# MCU.net
KiCad netlist of a schematic drawn in Altium Designer
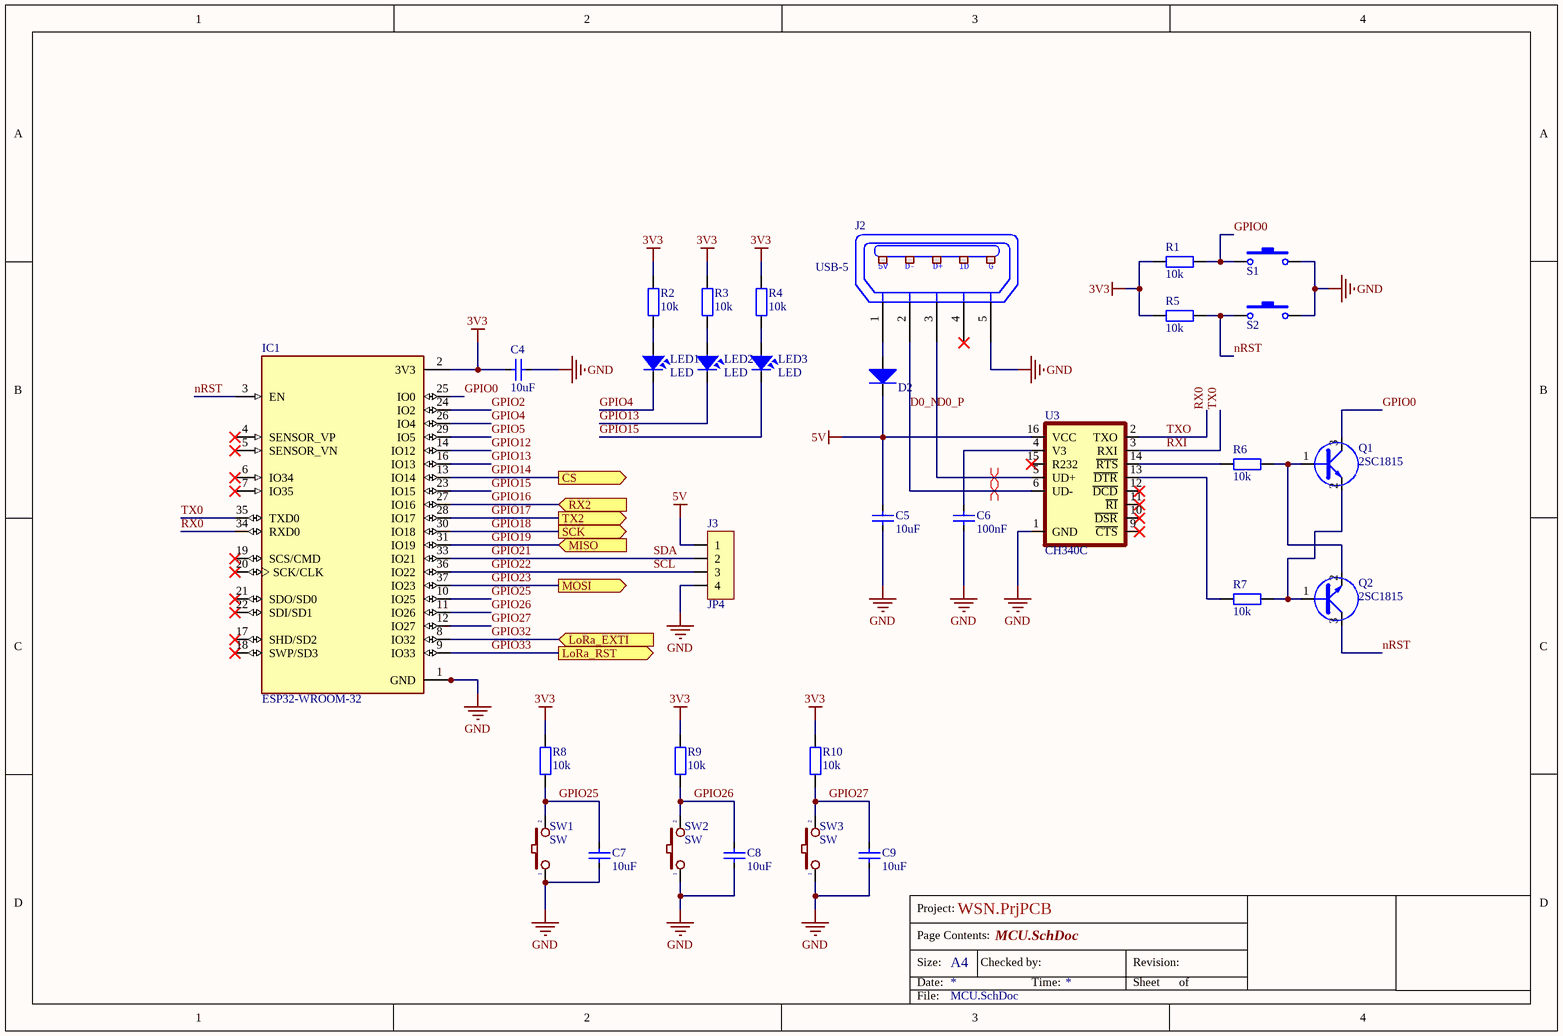
[diagram p0: MCU.SchDoc]

(export (version "E")
  (design (tool "Eeschema 10.0.6"))
  (components
    (comp (ref "C4")
      (value "10uF")
      (footprint "CAP_0805")
      (description "Capacitor")
      (fields (field (name "PUBLISHER") "Altium Limited"))
      (libsource (lib "My Library") (part "CapSMD"))
    )
    (comp (ref "C5")
      (value "10uF")
      (footprint "CAP_0805")
      (description "Capacitor")
      (fields (field (name "PUBLISHER") "Altium Limited"))
      (libsource (lib "My Library") (part "CapSMD"))
    )
    (comp (ref "C6")
      (value "100nF")
      (footprint "CAP_0805")
      (description "Capacitor")
      (fields (field (name "PUBLISHER") "Altium Limited"))
      (libsource (lib "My Library") (part "CapSMD"))
    )
    (comp (ref "C7")
      (value "10uF")
      (footprint "CAP_0805")
      (description "Capacitor")
      (fields (field (name "PUBLISHER") "Altium Limited"))
      (libsource (lib "My Library") (part "CapSMD"))
    )
    (comp (ref "C8")
      (value "10uF")
      (footprint "CAP_0805")
      (description "Capacitor")
      (fields (field (name "PUBLISHER") "Altium Limited"))
      (libsource (lib "My Library") (part "CapSMD"))
    )
    (comp (ref "C9")
      (value "10uF")
      (footprint "CAP_0805")
      (description "Capacitor")
      (fields (field (name "PUBLISHER") "Altium Limited"))
      (libsource (lib "My Library") (part "CapSMD"))
    )
    (comp (ref "D2")
      (value "Diode SMD")
      (footprint "DIO-214AC(SMA)")
      (description "Default Diode")
      (fields (field (name "PUBLISHER") "Altium Limited"))
      (libsource (lib "My Library") (part "Diode SMD"))
    )
    (comp (ref "IC1")
      (value "ESP32-WROOM-32")
      (footprint "MODULE_ESP32-WROOM-32")
      (description "Bluetooth, WiFi Transceiver Module 2.4GHz ~ 2.5GHz Surface Mount")
      (fields (field (name "MF") "Espressif Systems") (field (name "DIGI-KEY_PART_NUMBER") "1904-1010-1-ND"))
      (libsource (lib "My Library") (part "ESP32-WROOM-32"))
    )
    (comp (ref "J2")
      (value "USB-5")
      (footprint "USB-M1")
      (fields
        (field (name "MANUFACTURER") "FCI")
        (field (name "MANUFACTURER PART NUMBER") "10118193-0001LF")
        (field (name ".CREATOR") "MM")
        (field (name ".CHECKED PCB") "RF")
        (field (name ".CHECKED SCH") "MM")
      )
      (libsource (lib "My Library") (part "USB-5"))
    )
    (comp (ref "J3")
      (value "JP4")
      (footprint "JP4-C1T")
      (description "WR-PHD 2.54 mm Angled Socket Header")
      (fields
        (field (name "MANUFACTURER") "Würth Elektronik eiSos GmbH")
        (field (name "PARTNO") "613004143121")
        (field (name "CREATED BY") "Karrer Zheng")
      )
      (libsource (lib "My Library") (part "JP4"))
    )
    (comp (ref "LED1")
      (value "LED")
      (footprint "LED-0805-Orange")
      (description "LED Single colour Green and Red")
      (libsource (lib "My Library") (part "LED"))
    )
    (comp (ref "LED2")
      (value "LED")
      (footprint "LED-0805-Orange")
      (description "LED Single colour Green and Red")
      (libsource (lib "My Library") (part "LED"))
    )
    (comp (ref "LED3")
      (value "LED")
      (footprint "LED-0805-Orange")
      (description "LED Single colour Green and Red")
      (libsource (lib "My Library") (part "LED"))
    )
    (comp (ref "Q1")
      (value "2SC1815")
      (footprint "SOT23D")
      (description "NPN 600mW, ECB")
      (libsource (lib "My Library") (part "C1815"))
    )
    (comp (ref "Q2")
      (value "2SC1815")
      (footprint "SOT23D")
      (description "NPN 600mW, ECB")
      (libsource (lib "") (part "C1815_1"))
    )
    (comp (ref "R1")
      (value "10k")
      (footprint "RES-SMD-0805")
      (description "Resistor SMD")
      (fields
        (field (name "MANUFACTURER") "Generic Components")
        (field (name "PUBLISHER") "Altium Hobart Technology Centre")
      )
      (libsource (lib "My Library") (part "Resistor - SMD"))
    )
    (comp (ref "R2")
      (value "10k")
      (footprint "RES-SMD-0805")
      (description "Resistor SMD")
      (fields
        (field (name "MANUFACTURER") "Generic Components")
        (field (name "PUBLISHER") "Altium Hobart Technology Centre")
      )
      (libsource (lib "My Library") (part "Resistor - SMD"))
    )
    (comp (ref "R3")
      (value "10k")
      (footprint "RES-SMD-0805")
      (description "Resistor SMD")
      (fields
        (field (name "MANUFACTURER") "Generic Components")
        (field (name "PUBLISHER") "Altium Hobart Technology Centre")
      )
      (libsource (lib "My Library") (part "Resistor - SMD"))
    )
    (comp (ref "R4")
      (value "10k")
      (footprint "RES-SMD-0805")
      (description "Resistor SMD")
      (fields
        (field (name "MANUFACTURER") "Generic Components")
        (field (name "PUBLISHER") "Altium Hobart Technology Centre")
      )
      (libsource (lib "My Library") (part "Resistor - SMD"))
    )
    (comp (ref "R5")
      (value "10k")
      (footprint "RES-SMD-0805")
      (description "Resistor SMD")
      (fields
        (field (name "MANUFACTURER") "Generic Components")
        (field (name "PUBLISHER") "Altium Hobart Technology Centre")
      )
      (libsource (lib "My Library") (part "Resistor - SMD"))
    )
    (comp (ref "R6")
      (value "10k")
      (footprint "RES-SMD-0805")
      (description "Resistor SMD")
      (fields
        (field (name "MANUFACTURER") "Generic Components")
        (field (name "PUBLISHER") "Altium Hobart Technology Centre")
      )
      (libsource (lib "My Library") (part "Resistor - SMD"))
    )
    (comp (ref "R7")
      (value "10k")
      (footprint "RES-SMD-0805")
      (description "Resistor SMD")
      (fields
        (field (name "MANUFACTURER") "Generic Components")
        (field (name "PUBLISHER") "Altium Hobart Technology Centre")
      )
      (libsource (lib "My Library") (part "Resistor - SMD"))
    )
    (comp (ref "R8")
      (value "10k")
      (footprint "RES-SMD-0805")
      (description "Resistor SMD")
      (fields
        (field (name "MANUFACTURER") "Generic Components")
        (field (name "PUBLISHER") "Altium Hobart Technology Centre")
      )
      (libsource (lib "My Library") (part "Resistor - SMD"))
    )
    (comp (ref "R9")
      (value "10k")
      (footprint "RES-SMD-0805")
      (description "Resistor SMD")
      (fields
        (field (name "MANUFACTURER") "Generic Components")
        (field (name "PUBLISHER") "Altium Hobart Technology Centre")
      )
      (libsource (lib "My Library") (part "Resistor - SMD"))
    )
    (comp (ref "R10")
      (value "10k")
      (footprint "RES-SMD-0805")
      (description "Resistor SMD")
      (fields
        (field (name "MANUFACTURER") "Generic Components")
        (field (name "PUBLISHER") "Altium Hobart Technology Centre")
      )
      (libsource (lib "My Library") (part "Resistor - SMD"))
    )
    (comp (ref "S1")
      (value "SW-SMD")
      (footprint "SW 3x2x4")
      (description "Switch")
      (fields (field (name "PUBLISHER") "Altium Limited"))
      (libsource (lib "My Library") (part "SW-SMD"))
    )
    (comp (ref "S2")
      (value "SW-SMD")
      (footprint "SW 3x2x4")
      (description "Switch")
      (fields (field (name "PUBLISHER") "Altium Limited"))
      (libsource (lib "My Library") (part "SW-SMD"))
    )
    (comp (ref "SW1")
      (value "SW")
      (footprint "SW2")
      (description "Switch button 2 pin")
      (libsource (lib "My Library") (part "SW2"))
    )
    (comp (ref "SW2")
      (value "SW")
      (footprint "SW2")
      (description "Switch button 2 pin")
      (libsource (lib "My Library") (part "SW2"))
    )
    (comp (ref "SW3")
      (value "SW")
      (footprint "SW2")
      (description "Switch button 2 pin")
      (libsource (lib "My Library") (part "SW2"))
    )
    (comp (ref "U3")
      (value "CH340C")
      (footprint "SOP-16")
      (description "USB to serial chip CH340")
      (fields (field (name "MF") "WCH"))
      (libsource (lib "My Library") (part "CH340C"))
    )
  )
  (nets
    (net (code "1") (name "/D0_N") (class "Default")
      (node (ref "J2") (pin "2") (pinfunction "P2_2") (pintype "passive"))
      (node (ref "U3") (pin "6") (pinfunction "UD-_6") (pintype "bidirectional"))
    )
    (net (code "2") (name "/D0_P") (class "Default")
      (node (ref "J2") (pin "3") (pinfunction "P3_3") (pintype "passive"))
      (node (ref "U3") (pin "5") (pinfunction "UD+_5") (pintype "bidirectional"))
    )
    (net (code "3") (name "/GPIO0") (class "Default")
      (node (ref "IC1") (pin "25") (pinfunction "IO0_25") (pintype "bidirectional"))
      (node (ref "Q1") (pin "3") (pinfunction "C_3") (pintype "passive"))
      (node (ref "R1") (pin "1") (pinfunction "1_1") (pintype "passive"))
      (node (ref "S1") (pin "1") (pinfunction "1_1") (pintype "passive"))
    )
    (net (code "4") (name "/GPIO2") (class "Default")
      (node (ref "IC1") (pin "24") (pinfunction "IO2_24") (pintype "bidirectional"))
    )
    (net (code "5") (name "/GPIO4") (class "Default")
      (node (ref "IC1") (pin "26") (pinfunction "IO4_26") (pintype "bidirectional"))
      (node (ref "LED1") (pin "2") (pinfunction "2_2") (pintype "passive"))
    )
    (net (code "6") (name "/GPIO5") (class "Default")
      (node (ref "IC1") (pin "29") (pinfunction "IO5_29") (pintype "bidirectional"))
    )
    (net (code "7") (name "/GPIO12") (class "Default")
      (node (ref "IC1") (pin "14") (pinfunction "IO12_14") (pintype "bidirectional"))
    )
    (net (code "8") (name "/GPIO13") (class "Default")
      (node (ref "IC1") (pin "16") (pinfunction "IO13_16") (pintype "bidirectional"))
      (node (ref "LED2") (pin "2") (pinfunction "2_2") (pintype "passive"))
    )
    (net (code "9") (name "/GPIO14") (class "Default")
      (node (ref "IC1") (pin "13") (pinfunction "IO14_13") (pintype "bidirectional"))
    )
    (net (code "10") (name "/GPIO15") (class "Default")
      (node (ref "IC1") (pin "23") (pinfunction "IO15_23") (pintype "bidirectional"))
      (node (ref "LED3") (pin "2") (pinfunction "2_2") (pintype "passive"))
    )
    (net (code "11") (name "/GPIO16") (class "Default")
      (node (ref "IC1") (pin "27") (pinfunction "IO16_27") (pintype "bidirectional"))
    )
    (net (code "12") (name "/GPIO17") (class "Default")
      (node (ref "IC1") (pin "28") (pinfunction "IO17_28") (pintype "bidirectional"))
    )
    (net (code "13") (name "/GPIO18") (class "Default")
      (node (ref "IC1") (pin "30") (pinfunction "IO18_30") (pintype "bidirectional"))
    )
    (net (code "14") (name "/GPIO19") (class "Default")
      (node (ref "IC1") (pin "31") (pinfunction "IO19_31") (pintype "bidirectional"))
    )
    (net (code "15") (name "/GPIO21") (class "Default")
      (node (ref "IC1") (pin "33") (pinfunction "IO21_33") (pintype "bidirectional"))
      (node (ref "J3") (pin "2") (pinfunction "2_2") (pintype "passive"))
    )
    (net (code "16") (name "/GPIO22") (class "Default")
      (node (ref "IC1") (pin "36") (pinfunction "IO22_36") (pintype "bidirectional"))
      (node (ref "J3") (pin "3") (pinfunction "3_3") (pintype "passive"))
    )
    (net (code "17") (name "/GPIO23") (class "Default")
      (node (ref "IC1") (pin "37") (pinfunction "IO23_37") (pintype "bidirectional"))
    )
    (net (code "18") (name "/GPIO25") (class "Default")
      (node (ref "C7") (pin "2") (pinfunction "2_2") (pintype "passive"))
      (node (ref "IC1") (pin "10") (pinfunction "IO25_10") (pintype "bidirectional"))
      (node (ref "R8") (pin "2") (pinfunction "2_2") (pintype "passive"))
      (node (ref "SW1") (pin "2") (pinfunction "2_2") (pintype "passive"))
    )
    (net (code "19") (name "/GPIO26") (class "Default")
      (node (ref "C8") (pin "2") (pinfunction "2_2") (pintype "passive"))
      (node (ref "IC1") (pin "11") (pinfunction "IO26_11") (pintype "bidirectional"))
      (node (ref "R9") (pin "2") (pinfunction "2_2") (pintype "passive"))
      (node (ref "SW2") (pin "2") (pinfunction "2_2") (pintype "passive"))
    )
    (net (code "20") (name "/GPIO27") (class "Default")
      (node (ref "C9") (pin "2") (pinfunction "2_2") (pintype "passive"))
      (node (ref "IC1") (pin "12") (pinfunction "IO27_12") (pintype "bidirectional"))
      (node (ref "R10") (pin "2") (pinfunction "2_2") (pintype "passive"))
      (node (ref "SW3") (pin "2") (pinfunction "2_2") (pintype "passive"))
    )
    (net (code "21") (name "/GPIO32") (class "Default")
      (node (ref "IC1") (pin "8") (pinfunction "IO32_8") (pintype "bidirectional"))
    )
    (net (code "22") (name "/GPIO33") (class "Default")
      (node (ref "IC1") (pin "9") (pinfunction "IO33_9") (pintype "bidirectional"))
    )
    (net (code "23") (name "/RX0") (class "Default")
      (node (ref "IC1") (pin "34") (pinfunction "RXD0_34") (pintype "bidirectional"))
      (node (ref "U3") (pin "2") (pinfunction "TXO_2") (pintype "bidirectional"))
    )
    (net (code "24") (name "/RXI") (class "Default")
      (node (ref "IC1") (pin "35") (pinfunction "TXD0_35") (pintype "bidirectional"))
      (node (ref "U3") (pin "3") (pinfunction "RXI_3") (pintype "bidirectional"))
    )
    (net (code "25") (name "/nRST") (class "Default")
      (node (ref "IC1") (pin "3") (pinfunction "EN_3") (pintype "input"))
      (node (ref "Q2") (pin "3") (pinfunction "C_3") (pintype "passive"))
      (node (ref "R5") (pin "1") (pinfunction "1_1") (pintype "passive"))
      (node (ref "S2") (pin "1") (pinfunction "1_1") (pintype "passive"))
    )
    (net (code "26") (name "3V3") (class "Default")
      (node (ref "C4") (pin "2") (pinfunction "2_2") (pintype "passive"))
      (node (ref "IC1") (pin "2") (pinfunction "3V3_2") (pintype "power_in"))
      (node (ref "R1") (pin "2") (pinfunction "2_2") (pintype "passive"))
      (node (ref "R10") (pin "1") (pinfunction "1_1") (pintype "passive"))
      (node (ref "R2") (pin "1") (pinfunction "1_1") (pintype "passive"))
      (node (ref "R3") (pin "1") (pinfunction "1_1") (pintype "passive"))
      (node (ref "R4") (pin "1") (pinfunction "1_1") (pintype "passive"))
      (node (ref "R5") (pin "2") (pinfunction "2_2") (pintype "passive"))
      (node (ref "R8") (pin "1") (pinfunction "1_1") (pintype "passive"))
      (node (ref "R9") (pin "1") (pinfunction "1_1") (pintype "passive"))
    )
    (net (code "27") (name "5V") (class "Default")
      (node (ref "C5") (pin "2") (pinfunction "2_2") (pintype "passive"))
      (node (ref "D2") (pin "2") (pinfunction "K_2") (pintype "passive"))
      (node (ref "J3") (pin "1") (pinfunction "1_1") (pintype "passive"))
      (node (ref "U3") (pin "16") (pinfunction "VCC_16") (pintype "bidirectional"))
    )
    (net (code "28") (name "GND") (class "Default")
      (node (ref "C4") (pin "1") (pinfunction "1_1") (pintype "passive"))
      (node (ref "C5") (pin "1") (pinfunction "1_1") (pintype "passive"))
      (node (ref "C6") (pin "1") (pinfunction "1_1") (pintype "passive"))
      (node (ref "C7") (pin "1") (pinfunction "1_1") (pintype "passive"))
      (node (ref "C8") (pin "1") (pinfunction "1_1") (pintype "passive"))
      (node (ref "C9") (pin "1") (pinfunction "1_1") (pintype "passive"))
      (node (ref "IC1") (pin "1") (pinfunction "GND_1") (pintype "power_in"))
      (node (ref "IC1") (pin "15") (pinfunction "GND_15") (pintype "power_in"))
      (node (ref "IC1") (pin "38") (pinfunction "GND_38") (pintype "power_in"))
      (node (ref "IC1") (pin "39_1") (pinfunction "GND_39_1") (pintype "power_in"))
      (node (ref "IC1") (pin "39_10") (pinfunction "GND_39_10") (pintype "power_in"))
      (node (ref "IC1") (pin "39_11") (pinfunction "GND_39_11") (pintype "power_in"))
      (node (ref "IC1") (pin "39_12") (pinfunction "GND_39_12") (pintype "power_in"))
      (node (ref "IC1") (pin "39_13") (pinfunction "GND_39_13") (pintype "power_in"))
      (node (ref "IC1") (pin "39_14") (pinfunction "GND_39_14") (pintype "power_in"))
      (node (ref "IC1") (pin "39_15") (pinfunction "GND_39_15") (pintype "power_in"))
      (node (ref "IC1") (pin "39_16") (pinfunction "GND_39_16") (pintype "power_in"))
      (node (ref "IC1") (pin "39_17") (pinfunction "GND_39_17") (pintype "power_in"))
      (node (ref "IC1") (pin "39_18") (pinfunction "GND_39_18") (pintype "power_in"))
      (node (ref "IC1") (pin "39_19") (pinfunction "GND_39_19") (pintype "power_in"))
      (node (ref "IC1") (pin "39_2") (pinfunction "GND_39_2") (pintype "power_in"))
      (node (ref "IC1") (pin "39_20") (pinfunction "GND_39_20") (pintype "power_in"))
      (node (ref "IC1") (pin "39_21") (pinfunction "GND_39_21") (pintype "power_in"))
      (node (ref "IC1") (pin "39_3") (pinfunction "GND_39_3") (pintype "power_in"))
      (node (ref "IC1") (pin "39_4") (pinfunction "GND_39_4") (pintype "power_in"))
      (node (ref "IC1") (pin "39_5") (pinfunction "GND_39_5") (pintype "power_in"))
      (node (ref "IC1") (pin "39_6") (pinfunction "GND_39_6") (pintype "power_in"))
      (node (ref "IC1") (pin "39_7") (pinfunction "GND_39_7") (pintype "power_in"))
      (node (ref "IC1") (pin "39_8") (pinfunction "GND_39_8") (pintype "power_in"))
      (node (ref "IC1") (pin "39_9") (pinfunction "GND_39_9") (pintype "power_in"))
      (node (ref "J2") (pin "5") (pinfunction "P5_5") (pintype "passive"))
      (node (ref "J3") (pin "4") (pinfunction "4_4") (pintype "passive"))
      (node (ref "S1") (pin "2") (pinfunction "2_2") (pintype "passive"))
      (node (ref "S2") (pin "2") (pinfunction "2_2") (pintype "passive"))
      (node (ref "SW1") (pin "1") (pinfunction "1_1") (pintype "passive"))
      (node (ref "SW2") (pin "1") (pinfunction "1_1") (pintype "passive"))
      (node (ref "SW3") (pin "1") (pinfunction "1_1") (pintype "passive"))
      (node (ref "U3") (pin "1") (pinfunction "GND_1") (pintype "bidirectional"))
    )
    (net (code "29") (name "Net-(D2-A)") (class "Default")
      (node (ref "D2") (pin "1") (pinfunction "A_1") (pintype "passive"))
      (node (ref "J2") (pin "1") (pinfunction "P1_1") (pintype "passive"))
    )
    (net (code "30") (name "Net-(LED1-Pad1)") (class "Default")
      (node (ref "LED1") (pin "1") (pinfunction "1_1") (pintype "passive"))
      (node (ref "R2") (pin "2") (pinfunction "2_2") (pintype "passive"))
    )
    (net (code "31") (name "Net-(LED2-Pad1)") (class "Default")
      (node (ref "LED2") (pin "1") (pinfunction "1_1") (pintype "passive"))
      (node (ref "R3") (pin "2") (pinfunction "2_2") (pintype "passive"))
    )
    (net (code "32") (name "Net-(LED3-Pad1)") (class "Default")
      (node (ref "LED3") (pin "1") (pinfunction "1_1") (pintype "passive"))
      (node (ref "R4") (pin "2") (pinfunction "2_2") (pintype "passive"))
    )
    (net (code "33") (name "Net-(Q1-B)") (class "Default")
      (node (ref "Q1") (pin "1") (pinfunction "B_1") (pintype "passive"))
      (node (ref "Q2") (pin "2") (pinfunction "E_2") (pintype "passive"))
      (node (ref "R6") (pin "1") (pinfunction "1_1") (pintype "passive"))
    )
    (net (code "34") (name "Net-(Q1-E)") (class "Default")
      (node (ref "Q1") (pin "2") (pinfunction "E_2") (pintype "passive"))
      (node (ref "Q2") (pin "1") (pinfunction "B_1") (pintype "passive"))
      (node (ref "R7") (pin "1") (pinfunction "1_1") (pintype "passive"))
    )
    (net (code "35") (name "Net-(U3-V3)") (class "Default")
      (node (ref "C6") (pin "2") (pinfunction "2_2") (pintype "passive"))
      (node (ref "U3") (pin "4") (pinfunction "V3_4") (pintype "bidirectional"))
    )
    (net (code "36") (name "Net-(U3-~{DTR})") (class "Default")
      (node (ref "R7") (pin "2") (pinfunction "2_2") (pintype "passive"))
      (node (ref "U3") (pin "13") (pinfunction "~{DTR}_13") (pintype "bidirectional"))
    )
    (net (code "37") (name "Net-(U3-~{RTS})") (class "Default")
      (node (ref "R6") (pin "2") (pinfunction "2_2") (pintype "passive"))
      (node (ref "U3") (pin "14") (pinfunction "~{RTS}_14") (pintype "bidirectional"))
    )
    (net (code "38") (name "unconnected-(IC1-IO34-Pad6)") (class "Default")
      (node (ref "IC1") (pin "6") (pinfunction "IO34_6") (pintype "input+no_connect"))
    )
    (net (code "39") (name "unconnected-(IC1-IO35-Pad7)") (class "Default")
      (node (ref "IC1") (pin "7") (pinfunction "IO35_7") (pintype "input+no_connect"))
    )
    (net (code "40") (name "unconnected-(IC1-SCK{slash}CLK-Pad20)") (class "Default")
      (node (ref "IC1") (pin "20") (pinfunction "SCK/CLK_20") (pintype "bidirectional+no_connect"))
    )
    (net (code "41") (name "unconnected-(IC1-SCS{slash}CMD-Pad19)") (class "Default")
      (node (ref "IC1") (pin "19") (pinfunction "SCS/CMD_19") (pintype "bidirectional+no_connect"))
    )
    (net (code "42") (name "unconnected-(IC1-SDI{slash}SD1-Pad22)") (class "Default")
      (node (ref "IC1") (pin "22") (pinfunction "SDI/SD1_22") (pintype "bidirectional+no_connect"))
    )
    (net (code "43") (name "unconnected-(IC1-SDO{slash}SD0-Pad21)") (class "Default")
      (node (ref "IC1") (pin "21") (pinfunction "SDO/SD0_21") (pintype "bidirectional+no_connect"))
    )
    (net (code "44") (name "unconnected-(IC1-SENSOR_VN-Pad5)") (class "Default")
      (node (ref "IC1") (pin "5") (pinfunction "SENSOR_VN_5") (pintype "input+no_connect"))
    )
    (net (code "45") (name "unconnected-(IC1-SENSOR_VP-Pad4)") (class "Default")
      (node (ref "IC1") (pin "4") (pinfunction "SENSOR_VP_4") (pintype "input+no_connect"))
    )
    (net (code "46") (name "unconnected-(IC1-SHD{slash}SD2-Pad17)") (class "Default")
      (node (ref "IC1") (pin "17") (pinfunction "SHD/SD2_17") (pintype "bidirectional+no_connect"))
    )
    (net (code "47") (name "unconnected-(IC1-SWP{slash}SD3-Pad18)") (class "Default")
      (node (ref "IC1") (pin "18") (pinfunction "SWP/SD3_18") (pintype "bidirectional+no_connect"))
    )
    (net (code "48") (name "unconnected-(J2-P4-Pad4)") (class "Default")
      (node (ref "J2") (pin "4") (pinfunction "P4_4") (pintype "passive+no_connect"))
    )
    (net (code "49") (name "unconnected-(U3-R232-Pad15)") (class "Default")
      (node (ref "U3") (pin "15") (pinfunction "R232_15") (pintype "bidirectional+no_connect"))
    )
    (net (code "50") (name "unconnected-(U3-~{CTS}-Pad9)") (class "Default")
      (node (ref "U3") (pin "9") (pinfunction "~{CTS}_9") (pintype "bidirectional+no_connect"))
    )
    (net (code "51") (name "unconnected-(U3-~{DCD}-Pad12)") (class "Default")
      (node (ref "U3") (pin "12") (pinfunction "~{DCD}_12") (pintype "bidirectional+no_connect"))
    )
    (net (code "52") (name "unconnected-(U3-~{DSR}-Pad10)") (class "Default")
      (node (ref "U3") (pin "10") (pinfunction "~{DSR}_10") (pintype "bidirectional+no_connect"))
    )
    (net (code "53") (name "unconnected-(U3-~{RI}-Pad11)") (class "Default")
      (node (ref "U3") (pin "11") (pinfunction "~{RI}_11") (pintype "bidirectional+no_connect"))
    )
  )
)
